# CAN_Communications.net
KiCad netlist of a schematic drawn in Altium Designer
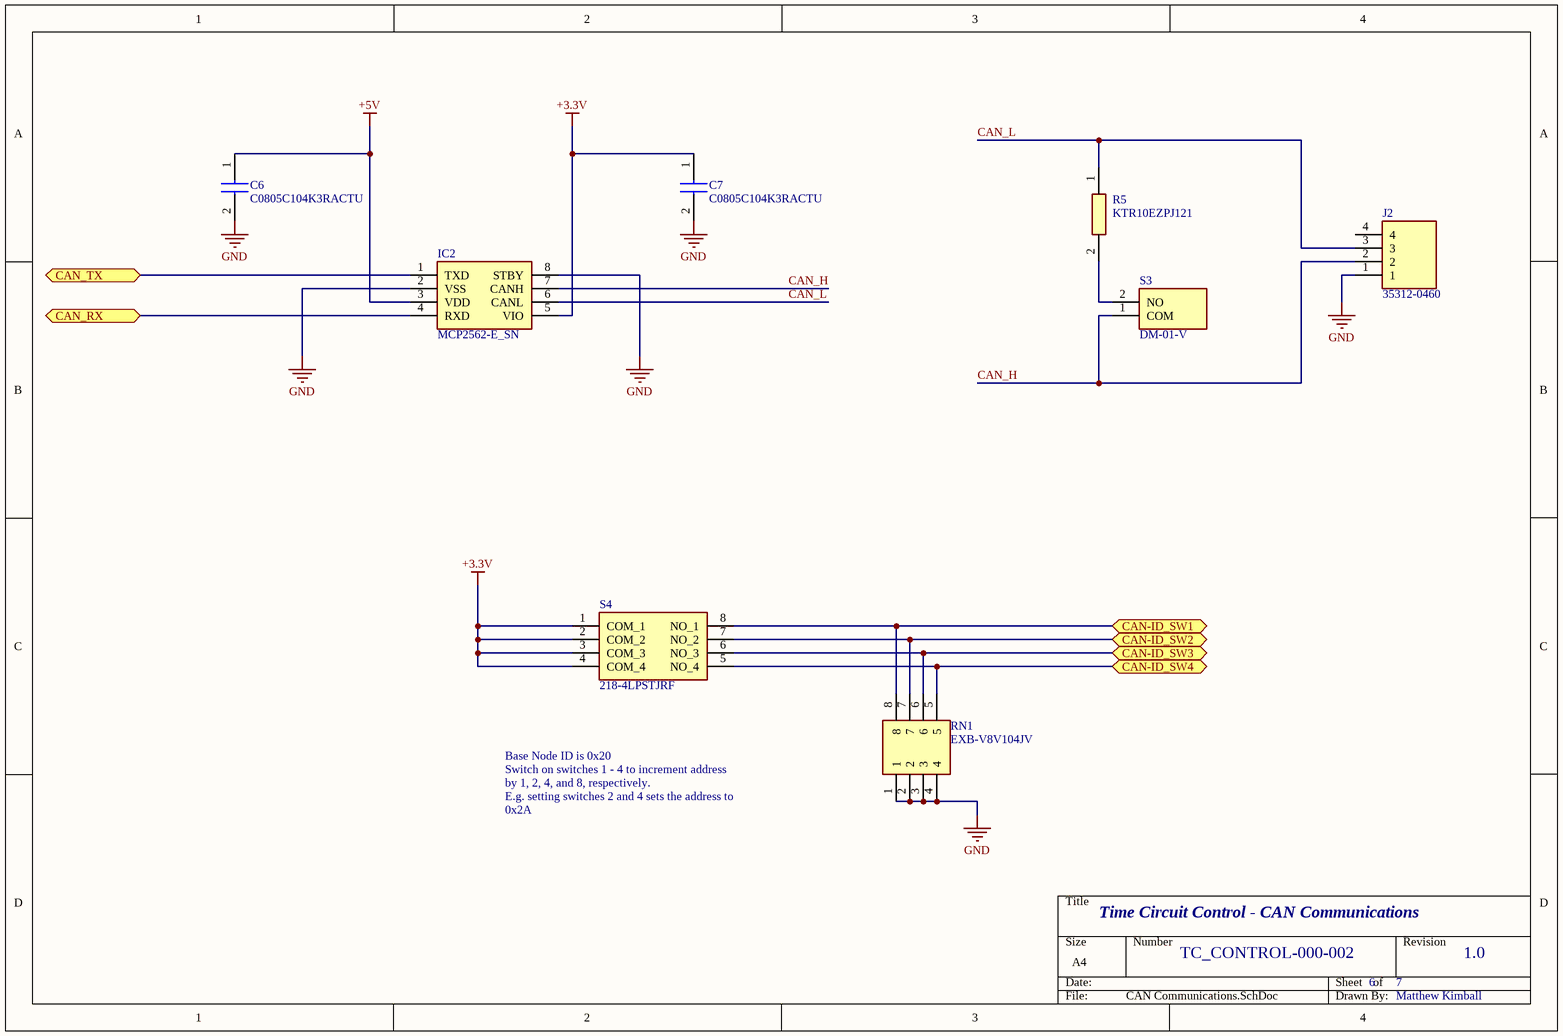
[diagram p0: CAN Communications.SchDoc]

(export (version "E")
  (design (tool "Eeschema 10.0.6"))
  (components
    (comp (ref "C6")
      (value "C0805C104K3RACTU")
      (footprint "SamacSys:CAPC2012X88N")
      (description "Capacitor")
      (fields (field (name "MOUSER PART NUMBER") "80-C0805C104K3R"))
      (libsource (lib "SamacSys") (part "C0805C104K3RACTU"))
    )
    (comp (ref "C7")
      (value "C0805C104K3RACTU")
      (footprint "SamacSys:CAPC2012X88N")
      (description "Capacitor")
      (fields (field (name "MOUSER PART NUMBER") "80-C0805C104K3R"))
      (libsource (lib "SamacSys") (part "C0805C104K3RACTU"))
    )
    (comp (ref "IC2")
      (value "MCP2562-E_SN")
      (footprint "SamacSys:SOIC127P600X175-8N")
      (description "Integrated Circuit")
      (fields
        (field (name "MANUFACTURER_PART_NUMBER") "MCP2562-E/SN")
        (field (name "MOUSER PART NUMBER") "579-MCP2562-E/SN")
      )
      (libsource (lib "SamacSys") (part "MCP2562-E_SN"))
    )
    (comp (ref "J2")
      (value "35312-0460")
      (footprint "SamacSys:SHDR4W64P0X250_1X4_1246X650X700P")
      (description "Connector")
      (fields (field (name "MOUSER PART NUMBER") "538-35312-0460"))
      (libsource (lib "SamacSys") (part "35312-0460"))
    )
    (comp (ref "R5")
      (value "KTR10EZPJ121")
      (footprint "SamacSys:RESC2012X65N")
      (description "Resistor")
      (fields (field (name "MOUSER PART NUMBER") "755-KTR10EZPJ121"))
      (libsource (lib "SamacSys") (part "KTR10EZPJ121"))
    )
    (comp (ref "RN1")
      (value "EXB-V8V104JV")
      (footprint "SamacSys:EXBV8V104JV")
      (description "Resistor Network")
      (fields (field (name "MOUSER PART NUMBER") "667-EXB-V8V104JV"))
      (libsource (lib "SamacSys") (part "EXB-V8V104JV"))
    )
    (comp (ref "S3")
      (value "DM-01-V")
      (footprint "SamacSys:DM01V")
      (description "Switch")
      (fields (field (name "MOUSER PART NUMBER") "113-DM01V"))
      (libsource (lib "SamacSys") (part "DM-01-V"))
    )
    (comp (ref "S4")
      (value "218-4LPSTJRF")
      (footprint "SamacSys:2184LPSTJRF")
      (description "Switch")
      (fields (field (name "MOUSER PART NUMBER") "774-218-4LPSTJRF"))
      (libsource (lib "SamacSys") (part "218-4LPSTJRF"))
    )
  )
  (nets
    (net (code "1") (name "+3.3V") (class "Default")
      (node (ref "C7") (pin "1") (pinfunction "1_1") (pintype "passive"))
      (node (ref "IC2") (pin "5") (pinfunction "VIO_5") (pintype "passive"))
      (node (ref "S4") (pin "1") (pinfunction "COM_1_1") (pintype "passive"))
      (node (ref "S4") (pin "2") (pinfunction "COM_2_2") (pintype "passive"))
      (node (ref "S4") (pin "3") (pinfunction "COM_3_3") (pintype "passive"))
      (node (ref "S4") (pin "4") (pinfunction "COM_4_4") (pintype "passive"))
    )
    (net (code "2") (name "+5V") (class "Default")
      (node (ref "C6") (pin "1") (pinfunction "1_1") (pintype "passive"))
      (node (ref "IC2") (pin "3") (pinfunction "VDD_3") (pintype "passive"))
    )
    (net (code "3") (name "/CAN-ID_SW1") (class "Default")
      (node (ref "RN1") (pin "8") (pinfunction "8_8") (pintype "passive"))
      (node (ref "S4") (pin "8") (pinfunction "NO_1_8") (pintype "passive"))
    )
    (net (code "4") (name "/CAN-ID_SW2") (class "Default")
      (node (ref "RN1") (pin "7") (pinfunction "7_7") (pintype "passive"))
      (node (ref "S4") (pin "7") (pinfunction "NO_2_7") (pintype "passive"))
    )
    (net (code "5") (name "/CAN-ID_SW3") (class "Default")
      (node (ref "RN1") (pin "6") (pinfunction "6_6") (pintype "passive"))
      (node (ref "S4") (pin "6") (pinfunction "NO_3_6") (pintype "passive"))
    )
    (net (code "6") (name "/CAN-ID_SW4") (class "Default")
      (node (ref "RN1") (pin "5") (pinfunction "5_5") (pintype "passive"))
      (node (ref "S4") (pin "5") (pinfunction "NO_4_5") (pintype "passive"))
    )
    (net (code "7") (name "/CAN_H") (class "Default")
      (node (ref "IC2") (pin "7") (pinfunction "CANH_7") (pintype "passive"))
      (node (ref "J2") (pin "2") (pinfunction "2_2") (pintype "passive"))
      (node (ref "S3") (pin "1") (pinfunction "COM_1") (pintype "passive"))
    )
    (net (code "8") (name "/CAN_L") (class "Default")
      (node (ref "IC2") (pin "6") (pinfunction "CANL_6") (pintype "passive"))
      (node (ref "J2") (pin "3") (pinfunction "3_3") (pintype "passive"))
      (node (ref "R5") (pin "1") (pinfunction "1_1") (pintype "passive"))
    )
    (net (code "9") (name "/CAN_RX") (class "Default")
      (node (ref "IC2") (pin "4") (pinfunction "RXD_4") (pintype "passive"))
    )
    (net (code "10") (name "/CAN_TX") (class "Default")
      (node (ref "IC2") (pin "1") (pinfunction "TXD_1") (pintype "passive"))
    )
    (net (code "11") (name "GND") (class "Default")
      (node (ref "C6") (pin "2") (pinfunction "2_2") (pintype "passive"))
      (node (ref "C7") (pin "2") (pinfunction "2_2") (pintype "passive"))
      (node (ref "IC2") (pin "2") (pinfunction "VSS_2") (pintype "passive"))
      (node (ref "IC2") (pin "8") (pinfunction "STBY_8") (pintype "passive"))
      (node (ref "J2") (pin "1") (pinfunction "1_1") (pintype "passive"))
      (node (ref "RN1") (pin "1") (pinfunction "1_1") (pintype "passive"))
      (node (ref "RN1") (pin "2") (pinfunction "2_2") (pintype "passive"))
      (node (ref "RN1") (pin "3") (pinfunction "3_3") (pintype "passive"))
      (node (ref "RN1") (pin "4") (pinfunction "4_4") (pintype "passive"))
    )
    (net (code "12") (name "Net-(S3-NO)") (class "Default")
      (node (ref "R5") (pin "2") (pinfunction "2_2") (pintype "passive"))
      (node (ref "S3") (pin "2") (pinfunction "NO_2") (pintype "passive"))
    )
    (net (code "13") (name "unconnected-(J2-Pad4)") (class "Default")
      (node (ref "J2") (pin "4") (pinfunction "4_4") (pintype "passive"))
    )
  )
)
